# SensorBoard.net
KiCad netlist of a schematic drawn in Altium Designer
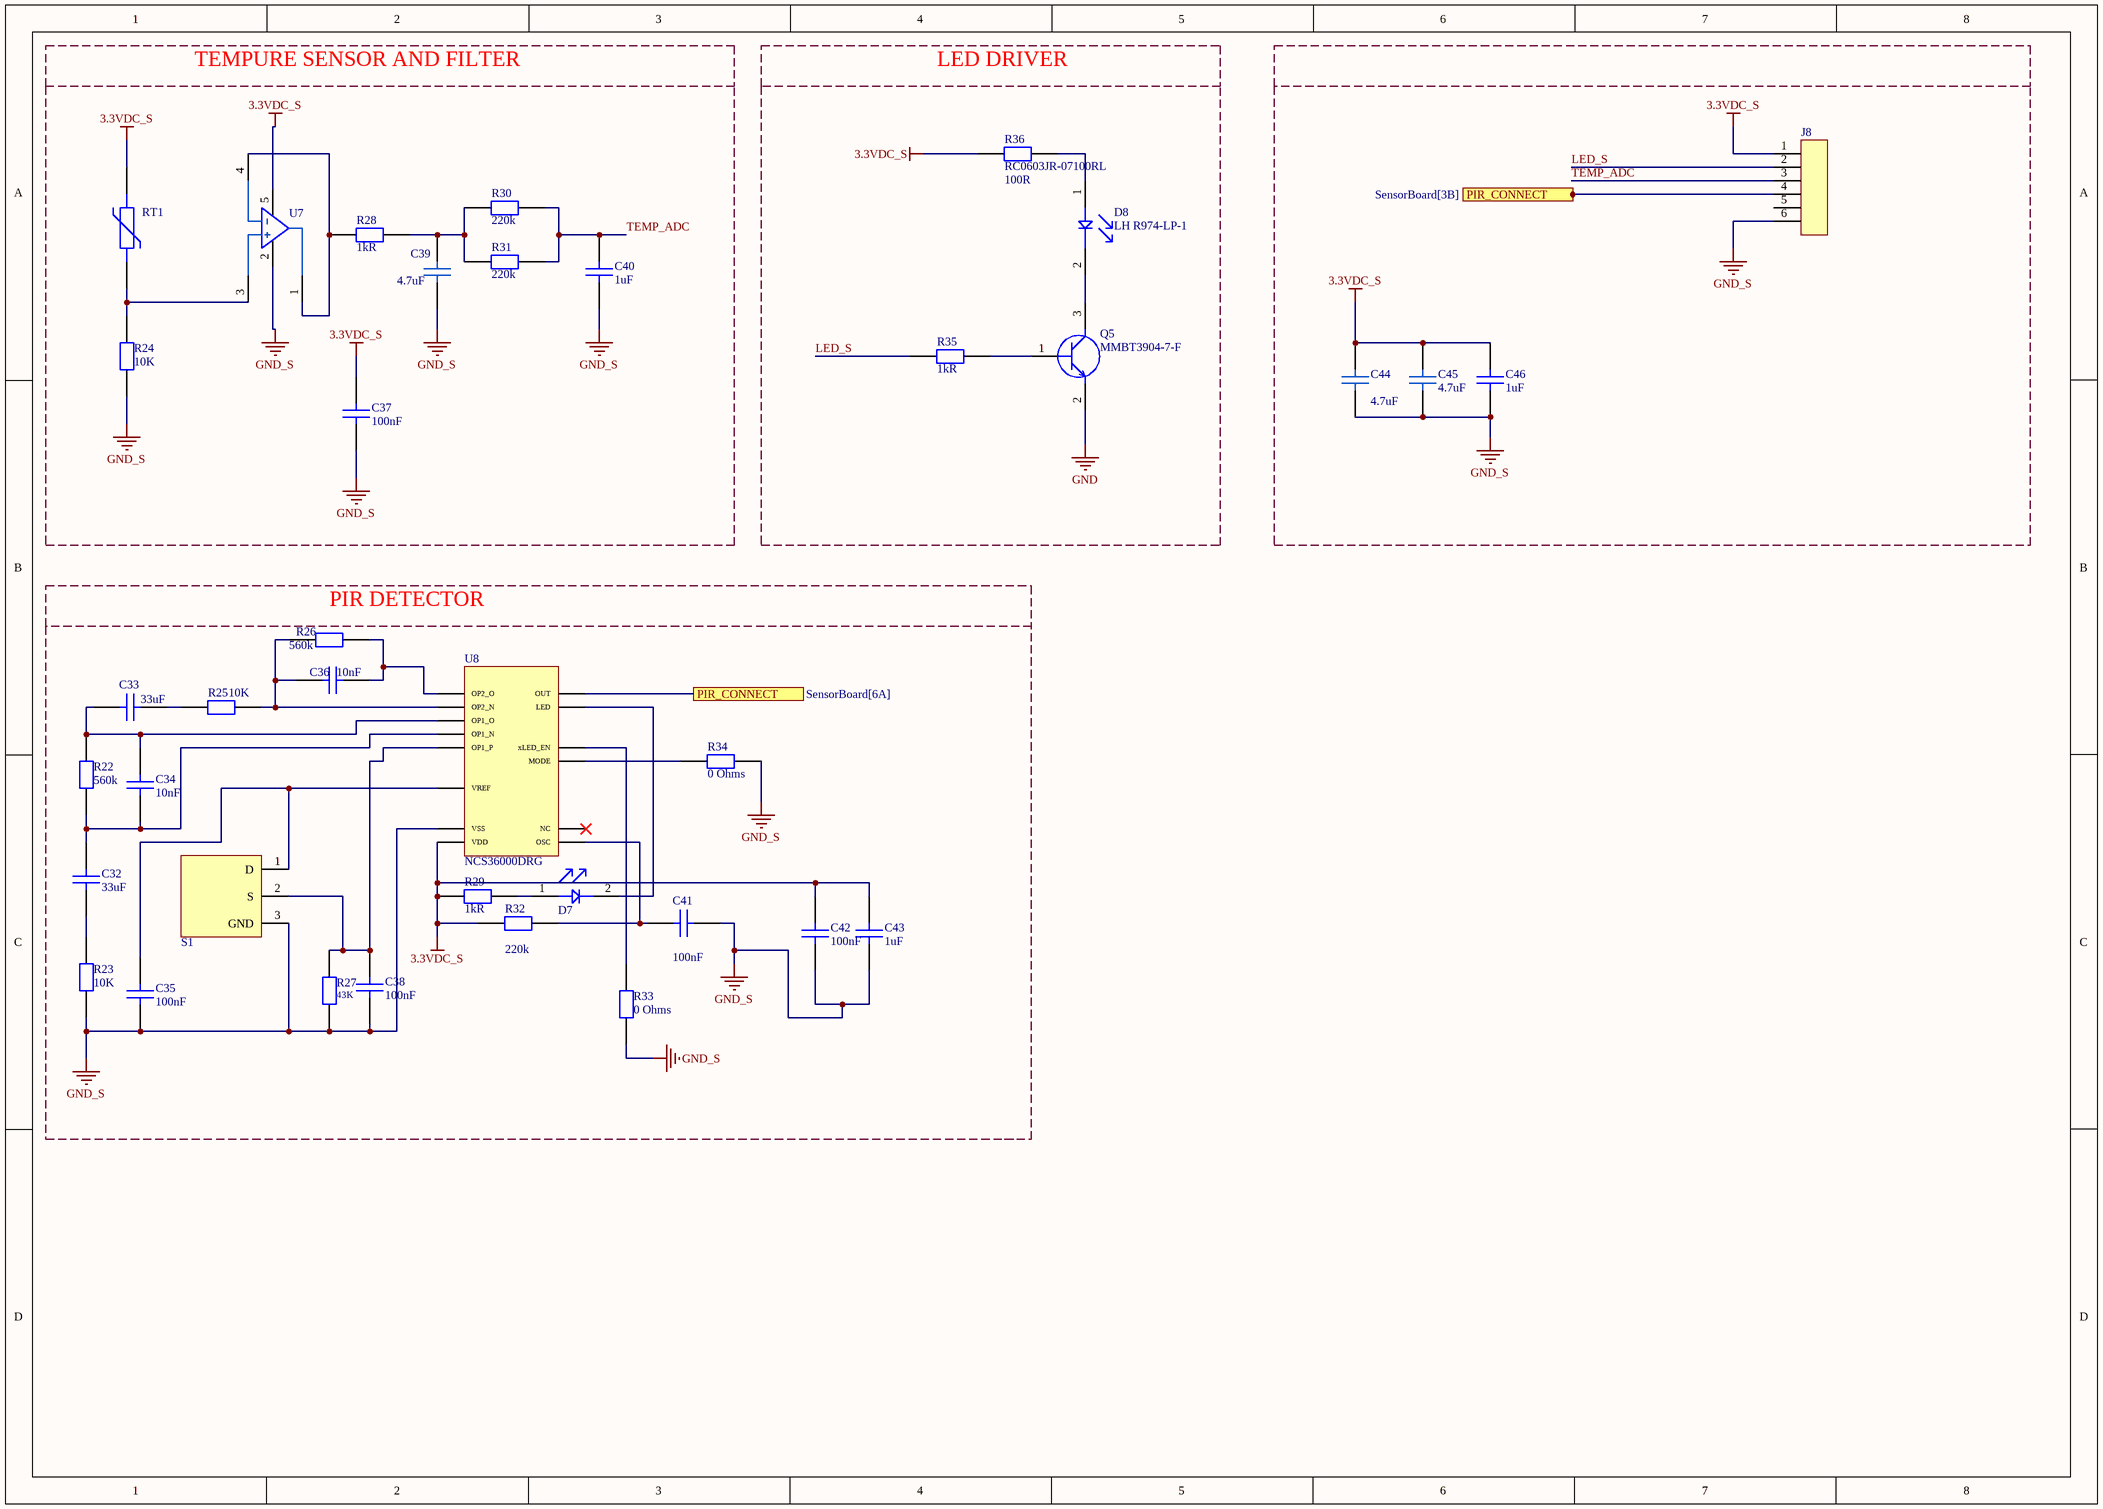
[diagram p0: SensorBoard.SchDoc]

(export (version "E")
  (design (tool "Eeschema 10.0.6"))
  (components
    (comp (ref "C32")
      (value "CAP CER 33UF 25V X5R 1206")
      (footprint "CAP 1206")
      (description "C Series 1206 33 uF 25 V ±20 % Tolerance X5R SMT Multilayer Ceramic Capacitor")
      (fields
        (field (name "MANUFACTURER") "TDK")
        (field (name "MANUFACTURER PART NUMBER") "C3216X5R1E336M160AC")
        (field (name "CAPACITANCE") "33uF")
      )
      (libsource (lib "ComplexCurcuit") (part "CAP CER 33uF 1206"))
    )
    (comp (ref "C33")
      (value "CAP CER 33UF 25V X5R 1206")
      (footprint "CAP 1206")
      (description "C Series 1206 33 uF 25 V ±20 % Tolerance X5R SMT Multilayer Ceramic Capacitor")
      (fields
        (field (name "MANUFACTURER") "TDK")
        (field (name "MANUFACTURER PART NUMBER") "C3216X5R1E336M160AC")
        (field (name "CAPACITANCE") "33uF")
      )
      (libsource (lib "ComplexCurcuit") (part "CAP CER 33uF 1206"))
    )
    (comp (ref "C34")
      (value "0603B103K160CT")
      (footprint "CAP 0603")
      (description "Multilayer Ceramic Capacitor, 0.01 F, 10%, X7R, 16 V, 0603 [1608 Metric] RoHS Compliant: Yes")
      (fields (field (name "MANUFACTURER") "Walsin Technologies") (field (name "CAPACITY") "10nF"))
      (libsource (lib "ComplexCurcuit") (part "CAP CER 10nF"))
    )
    (comp (ref "C35")
      (value "100nF")
      (footprint "CAP 0805")
      (description "Multilayer Ceramic Capacitor, 0.1 uF, 50 V, ± 10%, X7R, 0805 [2012 Metric]")
      (fields
        (field (name "MANUFACTURER") "Samsung")
        (field (name "MANUFACTURER PART NUMBER") "CL21B104KBCNNNC")
      )
      (libsource (lib "ComplexCurcuit") (part "CAP CER 100nF 0805"))
    )
    (comp (ref "C36")
      (value "0603B103K160CT")
      (footprint "CAP 0603")
      (description "Multilayer Ceramic Capacitor, 0.01 F, 10%, X7R, 16 V, 0603 [1608 Metric] RoHS Compliant: Yes")
      (fields (field (name "MANUFACTURER") "Walsin Technologies") (field (name "CAPACITY") "10nF"))
      (libsource (lib "ComplexCurcuit") (part "CAP CER 10nF"))
    )
    (comp (ref "C37")
      (value "CAP CER 100nF")
      (footprint "CAP 0603")
      (description "Cap Cer 0.1UF 16V X7R 0603 %10")
      (fields
        (field (name "MANUFACTURER") "KEMET")
        (field (name "MANUFACTURER PART NUMBER") "C0603C104K4RAC7082")
        (field (name "CAPACITANCE") "100nF")
        (field (name "DESIGNED BY") "Görkem Bulut")
      )
      (libsource (lib "ComplexCurcuit") (part "CAP CER 100nF"))
    )
    (comp (ref "C38")
      (value "100nF")
      (footprint "CAP 0805")
      (description "Multilayer Ceramic Capacitor, 0.1 uF, 50 V, ± 10%, X7R, 0805 [2012 Metric]")
      (fields
        (field (name "MANUFACTURER") "Samsung")
        (field (name "MANUFACTURER PART NUMBER") "CL21B104KBCNNNC")
      )
      (libsource (lib "ComplexCurcuit") (part "CAP CER 100nF 0805"))
    )
    (comp (ref "C39")
      (value "4.7uF")
      (footprint "CAP 0805")
      (description "CAP CER 4.7UF 25V X5R 0805")
      (fields
        (field (name "MANUFACTURER") "Samsung")
        (field (name "MANUFACTURER PART NUMBER") "CL21A475KAQNNNE")
      )
      (libsource (lib "ComplexCurcuit") (part "CAP CER 4.7uF"))
    )
    (comp (ref "C40")
      (value "CAP CER 1UF 50V X7R 0805")
      (footprint "CAP 0805")
      (fields
        (field (name "MANUFACTURER") "Samsung")
        (field (name "MANUFACTURER PART NUMBER") "CL21B105KBFNNNE")
        (field (name "CAPACITANCE") "1uF")
        (field (name "DESIGNED BY") "Görkem Bulut")
      )
      (libsource (lib "ComplexCurcuit") (part "CAP CER 1uF"))
    )
    (comp (ref "C41")
      (value "100nF")
      (footprint "CAP 0805")
      (description "Multilayer Ceramic Capacitor, 0.1 uF, 50 V, ± 10%, X7R, 0805 [2012 Metric]")
      (fields
        (field (name "MANUFACTURER") "Samsung")
        (field (name "MANUFACTURER PART NUMBER") "CL21B104KBCNNNC")
      )
      (libsource (lib "ComplexCurcuit") (part "CAP CER 100nF 0805"))
    )
    (comp (ref "C42")
      (value "100nF")
      (footprint "CAP 0805")
      (description "Multilayer Ceramic Capacitor, 0.1 uF, 50 V, ± 10%, X7R, 0805 [2012 Metric]")
      (fields
        (field (name "MANUFACTURER") "Samsung")
        (field (name "MANUFACTURER PART NUMBER") "CL21B104KBCNNNC")
      )
      (libsource (lib "ComplexCurcuit") (part "CAP CER 100nF 0805"))
    )
    (comp (ref "C43")
      (value "CAP CER 1UF 50V X7R 0805")
      (footprint "CAP 0805")
      (fields
        (field (name "MANUFACTURER") "Samsung")
        (field (name "MANUFACTURER PART NUMBER") "CL21B105KBFNNNE")
        (field (name "CAPACITANCE") "1uF")
        (field (name "DESIGNED BY") "Görkem Bulut")
      )
      (libsource (lib "ComplexCurcuit") (part "CAP CER 1uF"))
    )
    (comp (ref "C44")
      (value "4.7uF")
      (footprint "CAP 0805")
      (description "CAP CER 4.7UF 25V X5R 0805")
      (fields
        (field (name "MANUFACTURER") "Samsung")
        (field (name "MANUFACTURER PART NUMBER") "CL21A475KAQNNNE")
      )
      (libsource (lib "ComplexCurcuit") (part "CAP CER 4.7uF"))
    )
    (comp (ref "C45")
      (value "4.7uF")
      (footprint "CAP 0805")
      (description "CAP CER 4.7UF 25V X5R 0805")
      (fields
        (field (name "MANUFACTURER") "Samsung")
        (field (name "MANUFACTURER PART NUMBER") "CL21A475KAQNNNE")
      )
      (libsource (lib "ComplexCurcuit") (part "CAP CER 4.7uF"))
    )
    (comp (ref "C46")
      (value "CAP CER 1UF 50V X7R 0805")
      (footprint "CAP 0805")
      (fields
        (field (name "MANUFACTURER") "Samsung")
        (field (name "MANUFACTURER PART NUMBER") "CL21B105KBFNNNE")
        (field (name "CAPACITANCE") "1uF")
        (field (name "DESIGNED BY") "Görkem Bulut")
      )
      (libsource (lib "ComplexCurcuit") (part "CAP CER 1uF"))
    )
    (comp (ref "D7")
      (value "LTST-C171GKT")
      (footprint "Chip LED 0805")
      (description "LED Low-Power Uni-Color Green 565nm 2.1V 2-Pin Chip LED T/R")
      (fields (field (name "MANUFACTURER") "Vishay Lite-On") (field (name "DESIGNED BY") "Görkem BULUT"))
      (libsource (lib "ComplexCurcuit") (part "LTST-C171GKT-GreenChipLed"))
    )
    (comp (ref "D8")
      (value "LH R974-LP-1")
      (footprint "Chip LED 0805")
      (description "Red 645nm LED Indication - Discrete 1.8V 0805 (2012 Metric)")
      (fields
        (field (name "MANUFACTURER") "ams-OSRAM USA INC.")
        (field (name "VOLTAGE") "1.8V")
        (field (name "DESIGNED BY") "Görkem Bulut")
      )
      (libsource (lib "ComplexCurcuit") (part "Led- LH R974-LP-1-Chip Led"))
    )
    (comp (ref "J8")
      (value "64800611622 Datasheet WR-WTB Male Vertical Shrouded Header")
      (footprint "64800611622 Connector-1x6 Male Header")
      (description "WR-WTB Wire-to-Board Connectors 1.50 mm")
      (fields
        (field (name "MANUFACTURER") "Wurth Electronics")
        (field (name "MANUFACTURER PART NUMBER") "64800611622")
        (field (name "DESIGNED BY") "Görkem Bulut")
      )
      (libsource (lib "ComplexCurcuit") (part "1x6 Male Header-64800611622 Connector"))
    )
    (comp (ref "Q5")
      (value "MMBT3904-7-F")
      (footprint "SOT23F")
      (description "Transistor General Purpose BJT NPN 40 Volt 0.2A Automotive 3-Pin SOT-23")
      (fields (field (name "MANUFACTURER") "Diodes Zetex") (field (name "DESIGNED BY") "Gökem Bulut"))
      (libsource (lib "ComplexCurcuit") (part "MMBT3904-7-F"))
    )
    (comp (ref "R22")
      (value "RC0603JR-07220KL")
      (footprint "RES 0603")
      (description "SMD Chip Resistor, 220 kOhm, ± 5%, 100 mW, 0603 [1608 Metric], Thick Film, General Purpose")
      (fields
        (field (name "MANUFACTURER") "Yageo")
        (field (name "RESISTANCE") "560k")
        (field (name "DESIGNED BY") "Görkem Bulut")
      )
      (libsource (lib "") (part "RES 560K OHM_1"))
    )
    (comp (ref "R23")
      (value "RES 10K OHM  06103")
      (footprint "RES 0603")
      (description "RES SMD 10K OHM 1% 1/10W 0603")
      (fields
        (field (name "MANUFACTURER") "Yageo")
        (field (name "MANUFACTURER PART NUMBER") "RC0603FR-0710KL")
        (field (name "RESISTANCE") "10K")
        (field (name "DESIGNED BY") "Görkem Bulut")
      )
      (libsource (lib "ComplexCurcuit") (part "RES 10K OHM  06103"))
    )
    (comp (ref "R24")
      (value "RES 10K OHM  06103")
      (footprint "RES 0603")
      (description "RES SMD 10K OHM 1% 1/10W 0603")
      (fields
        (field (name "MANUFACTURER") "Yageo")
        (field (name "MANUFACTURER PART NUMBER") "RC0603FR-0710KL")
        (field (name "RESISTANCE") "10K")
        (field (name "DESIGNED BY") "Görkem Bulut")
      )
      (libsource (lib "ComplexCurcuit") (part "RES 10K OHM  06103"))
    )
    (comp (ref "R25")
      (value "RES 10K OHM  06103")
      (footprint "RES 0603")
      (description "RES SMD 10K OHM 1% 1/10W 0603")
      (fields
        (field (name "MANUFACTURER") "Yageo")
        (field (name "MANUFACTURER PART NUMBER") "RC0603FR-0710KL")
        (field (name "RESISTANCE") "10K")
        (field (name "DESIGNED BY") "Görkem Bulut")
      )
      (libsource (lib "") (part "RES 10K OHM  06103_1"))
    )
    (comp (ref "R26")
      (value "RC0603JR-07220KL")
      (footprint "RES 0603")
      (description "SMD Chip Resistor, 220 kOhm, ± 5%, 100 mW, 0603 [1608 Metric], Thick Film, General Purpose")
      (fields
        (field (name "MANUFACTURER") "Yageo")
        (field (name "RESISTANCE") "560k")
        (field (name "DESIGNED BY") "Görkem Bulut")
      )
      (libsource (lib "ComplexCurcuit") (part "RES 560K OHM"))
    )
    (comp (ref "R27")
      (value "43K")
      (footprint "RES 0603")
      (description "Res Thick Film 0603 43K Ohm 5% 0.1W(1/10W) ±100ppm/°C Pad SMD T/R")
      (fields
        (field (name "MANUFACTURER") "Yageo")
        (field (name "MANUFACTURER PART NUMBER") "RC0603JR-0743KL")
        (field (name "DESIGNED BY") "Görkem Bulut")
      )
      (libsource (lib "ComplexCurcuit") (part "RES 43K"))
    )
    (comp (ref "R28")
      (value "1kR")
      (footprint "RES 0603")
      (description "SMD Chip Resistor, 1 kOhm, ± 1%, 100 mW, 0603 [1608 Metric], Thick Film, General Purpose")
      (fields
        (field (name "MANUFACTURER") "Yageo")
        (field (name "MANUFACTURER PART NUMBER") "RC0603FR-071KL")
        (field (name "DESIGNED BY") "Görkem B.")
      )
      (libsource (lib "ComplexCurcuit") (part "RES 1K OHM"))
    )
    (comp (ref "R29")
      (value "1kR")
      (footprint "RES 0603")
      (description "SMD Chip Resistor, 1 kOhm, ± 1%, 100 mW, 0603 [1608 Metric], Thick Film, General Purpose")
      (fields
        (field (name "MANUFACTURER") "Yageo")
        (field (name "MANUFACTURER PART NUMBER") "RC0603FR-071KL")
        (field (name "DESIGNED BY") "Görkem B.")
      )
      (libsource (lib "ComplexCurcuit") (part "RES 1K OHM"))
    )
    (comp (ref "R30")
      (value "RC0603JR-07220KL")
      (footprint "RES 0603")
      (description "SMD Chip Resistor, 220 kOhm, ± 5%, 100 mW, 0603 [1608 Metric], Thick Film, General Purpose")
      (fields
        (field (name "MANUFACTURER") "Yageo")
        (field (name "RESISTANCE") "220k")
        (field (name "DESIGNED BY") "G.B")
      )
      (libsource (lib "") (part "RES 220K OHM_1"))
    )
    (comp (ref "R31")
      (value "RC0603JR-07220KL")
      (footprint "RES 0603")
      (description "SMD Chip Resistor, 220 kOhm, ± 5%, 100 mW, 0603 [1608 Metric], Thick Film, General Purpose")
      (fields
        (field (name "MANUFACTURER") "Yageo")
        (field (name "RESISTANCE") "220k")
        (field (name "DESIGNED BY") "G.B")
      )
      (libsource (lib "") (part "RES 220K OHM_1"))
    )
    (comp (ref "R32")
      (value "RC0603JR-07220KL")
      (footprint "RES 0603")
      (description "SMD Chip Resistor, 220 kOhm, ± 5%, 100 mW, 0603 [1608 Metric], Thick Film, General Purpose")
      (fields
        (field (name "MANUFACTURER") "Yageo")
        (field (name "RESISTANCE") "220k")
        (field (name "DESIGNED BY") "G.B")
      )
      (libsource (lib "ComplexCurcuit") (part "RES 220K OHM"))
    )
    (comp (ref "R33")
      (value "RES 0 OHM JUMPER 1/10W 0603")
      (footprint "RES 0603")
      (description "Zero Ohm Resistor, Jumper, 0603 [1608 Metric], Thick Film, 100 mW, 1 A, Surface Mount")
      (fields
        (field (name "MANUFACTURER") "Yageo")
        (field (name "MANUFACTURER PART NUMBER") "RC0603JR-070RL")
        (field (name "RESISTANCE") "0 Ohms")
        (field (name "DESIGNED BY") "Görkem Bulut")
      )
      (libsource (lib "ComplexCurcuit") (part "RES 0 OHM 0603"))
    )
    (comp (ref "R34")
      (value "RES 0 OHM JUMPER 1/10W 0603")
      (footprint "RES 0603")
      (description "Zero Ohm Resistor, Jumper, 0603 [1608 Metric], Thick Film, 100 mW, 1 A, Surface Mount")
      (fields
        (field (name "MANUFACTURER") "Yageo")
        (field (name "MANUFACTURER PART NUMBER") "RC0603JR-070RL")
        (field (name "RESISTANCE") "0 Ohms")
        (field (name "DESIGNED BY") "Görkem Bulut")
      )
      (libsource (lib "") (part "RES 0 OHM 0603_1"))
    )
    (comp (ref "R35")
      (value "1kR")
      (footprint "RES 0603")
      (description "SMD Chip Resistor, 1 kOhm, ± 1%, 100 mW, 0603 [1608 Metric], Thick Film, General Purpose")
      (fields
        (field (name "MANUFACTURER") "Yageo")
        (field (name "MANUFACTURER PART NUMBER") "RC0603FR-071KL")
        (field (name "DESIGNED BY") "Görkem B.")
      )
      (libsource (lib "ComplexCurcuit") (part "RES 1K OHM"))
    )
    (comp (ref "R36")
      (value "RC0603JR-07100RL")
      (footprint "RES 0603")
      (description "Res Thick Film 0603 100 Ohm 5% 1/10W ±100ppm/°C Molded SMD SMD Paper T/R")
      (fields
        (field (name "MANUFACTURER") "Yageo")
        (field (name "TOLERANCE") "5%")
        (field (name "RESISTANCE") "100R")
        (field (name "DESIGNED BY") "G.B")
      )
      (libsource (lib "ComplexCurcuit") (part "RES 100 OHM"))
    )
    (comp (ref "RT1")
      (value "TFPT1206L1002FM")
      (footprint "RES 1206 Package")
      (description "Thermistor PTC 10K Ohm 1% 2-Pin 1206 Surface Mount Solder Pad T/R Automotive")
      (fields
        (field (name "MANUFACTURER") "Vishay Dale")
        (field (name "TOLERANCE") "1%")
        (field (name "DESIGNED BY") "Görkem BULUT")
      )
      (libsource (lib "ComplexCurcuit") (part "TFPT1206L1002FM"))
    )
    (comp (ref "S1")
      (value "LHI 878/3902")
      (footprint "LHI 878/3902")
      (description "SENSOR PYRO DETECTOR DUAL MOTION")
      (fields
        (field (name "MANUFACTURER") "Excelitas Technologies")
        (field (name "DESIGNED BY") "Görkem Bulut")
      )
      (libsource (lib "ComplexCurcuit") (part "LHI 878/3902"))
    )
    (comp (ref "U7")
      (value "IC OPAMP GP 1 CIRCUIT SOT23-5")
      (footprint "SOT23-5")
      (description "IC OPAMP GP 3MHZ RRO SOT23-5")
      (fields
        (field (name "MANUFACTURER") "Texas Instruments")
        (field (name "MANUFACTURER PART NUMBER") "OPA314AIDBVR")
        (field (name "DESIGNED BY") "Görkem Bulut")
      )
      (libsource (lib "ComplexCurcuit") (part "OPA314AIDBVR"))
    )
    (comp (ref "U8")
      (value "NCS36000DRG")
      (footprint "SOIC14")
      (description "NCS36000 Series Single 5.75V Passive Infrared Detector Controller (PIR) -SOIC-14")
      (fields (field (name "MANUFACTURER") "ON Semiconductor"))
      (libsource (lib "ComplexCurcuit") (part "NCS36000DRG"))
    )
  )
  (nets
    (net (code "1") (name "/LED_S") (class "Default")
      (node (ref "J8") (pin "2") (pinfunction "2_2") (pintype "passive"))
      (node (ref "R35") (pin "1") (pinfunction "1_1") (pintype "passive"))
    )
    (net (code "2") (name "/PIR_CONNECT") (class "Default")
      (node (ref "J8") (pin "4") (pinfunction "4_4") (pintype "passive"))
      (node (ref "U8") (pin "8") (pinfunction "OUT_8") (pintype "passive"))
    )
    (net (code "3") (name "/TEMP_ADC") (class "Default")
      (node (ref "C40") (pin "2") (pinfunction "2_2") (pintype "passive"))
      (node (ref "J8") (pin "3") (pinfunction "3_3") (pintype "passive"))
      (node (ref "R30") (pin "1") (pinfunction "1_1") (pintype "passive"))
      (node (ref "R31") (pin "1") (pinfunction "1_1") (pintype "passive"))
    )
    (net (code "4") (name "3.3VDC_S") (class "Default")
      (node (ref "C37") (pin "2") (pinfunction "2_2") (pintype "passive"))
      (node (ref "C42") (pin "2") (pinfunction "2_2") (pintype "passive"))
      (node (ref "C43") (pin "2") (pinfunction "2_2") (pintype "passive"))
      (node (ref "C44") (pin "2") (pinfunction "2_2") (pintype "passive"))
      (node (ref "C45") (pin "2") (pinfunction "2_2") (pintype "passive"))
      (node (ref "C46") (pin "2") (pinfunction "2_2") (pintype "passive"))
      (node (ref "J8") (pin "1") (pinfunction "1_1") (pintype "passive"))
      (node (ref "R29") (pin "1") (pinfunction "1_1") (pintype "passive"))
      (node (ref "R32") (pin "1") (pinfunction "1_1") (pintype "passive"))
      (node (ref "R36") (pin "2") (pinfunction "2_2") (pintype "passive"))
      (node (ref "RT1") (pin "2") (pinfunction "2_2") (pintype "passive"))
      (node (ref "U7") (pin "5") (pinfunction "V+_5") (pintype "passive"))
      (node (ref "U8") (pin "14") (pinfunction "VDD_14") (pintype "passive"))
    )
    (net (code "5") (name "GND") (class "Default")
      (node (ref "Q5") (pin "2") (pinfunction "EMİTTER_2") (pintype "passive"))
    )
    (net (code "6") (name "GND_S") (class "Default")
      (node (ref "C35") (pin "1") (pinfunction "1_1") (pintype "passive"))
      (node (ref "C37") (pin "1") (pinfunction "1_1") (pintype "passive"))
      (node (ref "C38") (pin "1") (pinfunction "1_1") (pintype "passive"))
      (node (ref "C39") (pin "1") (pinfunction "1_1") (pintype "passive"))
      (node (ref "C40") (pin "1") (pinfunction "1_1") (pintype "passive"))
      (node (ref "C41") (pin "2") (pinfunction "2_2") (pintype "passive"))
      (node (ref "C42") (pin "1") (pinfunction "1_1") (pintype "passive"))
      (node (ref "C43") (pin "1") (pinfunction "1_1") (pintype "passive"))
      (node (ref "C44") (pin "1") (pinfunction "1_1") (pintype "passive"))
      (node (ref "C45") (pin "1") (pinfunction "1_1") (pintype "passive"))
      (node (ref "C46") (pin "1") (pinfunction "1_1") (pintype "passive"))
      (node (ref "J8") (pin "6") (pinfunction "6_6") (pintype "passive"))
      (node (ref "R23") (pin "1") (pinfunction "1_1") (pintype "passive"))
      (node (ref "R24") (pin "1") (pinfunction "1_1") (pintype "passive"))
      (node (ref "R27") (pin "1") (pinfunction "1_1") (pintype "passive"))
      (node (ref "R33") (pin "1") (pinfunction "1_1") (pintype "passive"))
      (node (ref "R34") (pin "1") (pinfunction "1_1") (pintype "passive"))
      (node (ref "S1") (pin "3") (pinfunction "GND_3") (pintype "passive"))
      (node (ref "U7") (pin "2") (pinfunction "V-_2") (pintype "passive"))
      (node (ref "U8") (pin "7") (pinfunction "VSS_7") (pintype "passive"))
    )
    (net (code "7") (name "Net-(C32-Pad1)") (class "Default")
      (node (ref "C32") (pin "1") (pinfunction "1_1") (pintype "passive"))
      (node (ref "R23") (pin "2") (pinfunction "2_2") (pintype "passive"))
    )
    (net (code "8") (name "Net-(C33-Pad2)") (class "Default")
      (node (ref "C33") (pin "2") (pinfunction "2_2") (pintype "passive"))
      (node (ref "R25") (pin "1") (pinfunction "1_1") (pintype "passive"))
    )
    (net (code "9") (name "Net-(C39-Pad2)") (class "Default")
      (node (ref "C39") (pin "2") (pinfunction "2_2") (pintype "passive"))
      (node (ref "R28") (pin "2") (pinfunction "2_2") (pintype "passive"))
      (node (ref "R30") (pin "2") (pinfunction "2_2") (pintype "passive"))
      (node (ref "R31") (pin "2") (pinfunction "2_2") (pintype "passive"))
    )
    (net (code "10") (name "Net-(D7-Pad1)") (class "Default")
      (node (ref "D7") (pin "1") (pinfunction "1_1") (pintype "passive"))
      (node (ref "R29") (pin "2") (pinfunction "2_2") (pintype "passive"))
    )
    (net (code "11") (name "Net-(D8-Pad1)") (class "Default")
      (node (ref "D8") (pin "1") (pinfunction "1_1") (pintype "passive"))
      (node (ref "R36") (pin "1") (pinfunction "1_1") (pintype "passive"))
    )
    (net (code "12") (name "Net-(Q5-BASE)") (class "Default")
      (node (ref "Q5") (pin "1") (pinfunction "BASE_1") (pintype "passive"))
      (node (ref "R35") (pin "2") (pinfunction "2_2") (pintype "passive"))
    )
    (net (code "13") (name "Net-(Q5-CONNECTOR)") (class "Default")
      (node (ref "D8") (pin "2") (pinfunction "2_2") (pintype "passive"))
      (node (ref "Q5") (pin "3") (pinfunction "CONNECTOR_3") (pintype "passive"))
    )
    (net (code "14") (name "Net-(S1-D)") (class "Default")
      (node (ref "C35") (pin "2") (pinfunction "2_2") (pintype "passive"))
      (node (ref "S1") (pin "1") (pinfunction "D_1") (pintype "passive"))
      (node (ref "U8") (pin "6") (pinfunction "VREF_6") (pintype "passive"))
    )
    (net (code "15") (name "Net-(S1-S)") (class "Default")
      (node (ref "C38") (pin "2") (pinfunction "2_2") (pintype "passive"))
      (node (ref "R27") (pin "2") (pinfunction "2_2") (pintype "passive"))
      (node (ref "S1") (pin "2") (pinfunction "S_2") (pintype "passive"))
      (node (ref "U8") (pin "5") (pinfunction "OP1_P_5") (pintype "passive"))
    )
    (net (code "16") (name "Net-(U7-+IN)") (class "Default")
      (node (ref "R24") (pin "2") (pinfunction "2_2") (pintype "passive"))
      (node (ref "RT1") (pin "1") (pinfunction "1_1") (pintype "passive"))
      (node (ref "U7") (pin "3") (pinfunction "+IN_3") (pintype "passive"))
    )
    (net (code "17") (name "Net-(U7-OUT)") (class "Default")
      (node (ref "R28") (pin "1") (pinfunction "1_1") (pintype "passive"))
      (node (ref "U7") (pin "1") (pinfunction "OUT_1") (pintype "passive"))
    )
    (net (code "18") (name "Net-(U8-LED)") (class "Default")
      (node (ref "D7") (pin "2") (pinfunction "2_2") (pintype "passive"))
      (node (ref "U8") (pin "9") (pinfunction "LED_9") (pintype "passive"))
    )
    (net (code "19") (name "Net-(U8-MODE)") (class "Default")
      (node (ref "R34") (pin "2") (pinfunction "2_2") (pintype "passive"))
      (node (ref "U8") (pin "12") (pinfunction "MODE_12") (pintype "passive"))
    )
    (net (code "20") (name "Net-(U8-OP1_N)") (class "Default")
      (node (ref "C32") (pin "2") (pinfunction "2_2") (pintype "passive"))
      (node (ref "C34") (pin "1") (pinfunction "1_1") (pintype "passive"))
      (node (ref "R22") (pin "1") (pinfunction "1_1") (pintype "passive"))
      (node (ref "U8") (pin "4") (pinfunction "OP1_N_4") (pintype "passive"))
    )
    (net (code "21") (name "Net-(U8-OP1_O)") (class "Default")
      (node (ref "C33") (pin "1") (pinfunction "1_1") (pintype "passive"))
      (node (ref "C34") (pin "2") (pinfunction "2_2") (pintype "passive"))
      (node (ref "R22") (pin "2") (pinfunction "2_2") (pintype "passive"))
      (node (ref "U8") (pin "3") (pinfunction "OP1_O_3") (pintype "passive"))
    )
    (net (code "22") (name "Net-(U8-OP2_N)") (class "Default")
      (node (ref "C36") (pin "1") (pinfunction "1_1") (pintype "passive"))
      (node (ref "R25") (pin "2") (pinfunction "2_2") (pintype "passive"))
      (node (ref "R26") (pin "1") (pinfunction "1_1") (pintype "passive"))
      (node (ref "U8") (pin "2") (pinfunction "OP2_N_2") (pintype "passive"))
    )
    (net (code "23") (name "Net-(U8-OP2_O)") (class "Default")
      (node (ref "C36") (pin "2") (pinfunction "2_2") (pintype "passive"))
      (node (ref "R26") (pin "2") (pinfunction "2_2") (pintype "passive"))
      (node (ref "U8") (pin "1") (pinfunction "OP2_O_1") (pintype "passive"))
    )
    (net (code "24") (name "Net-(U8-OSC)") (class "Default")
      (node (ref "C41") (pin "1") (pinfunction "1_1") (pintype "passive"))
      (node (ref "R32") (pin "2") (pinfunction "2_2") (pintype "passive"))
      (node (ref "U8") (pin "13") (pinfunction "OSC_13") (pintype "passive"))
    )
    (net (code "25") (name "Net-(U8-xLED_EN)") (class "Default")
      (node (ref "R33") (pin "2") (pinfunction "2_2") (pintype "passive"))
      (node (ref "U8") (pin "10") (pinfunction "xLED_EN_10") (pintype "passive"))
    )
    (net (code "26") (name "unconnected-(J8-Pad5)") (class "Default")
      (node (ref "J8") (pin "5") (pinfunction "5_5") (pintype "passive"))
    )
    (net (code "27") (name "unconnected-(U7--IN-Pad4)") (class "Default")
      (node (ref "U7") (pin "4") (pinfunction "-IN_4") (pintype "passive"))
    )
    (net (code "28") (name "unconnected-(U8-NC-Pad11)") (class "Default")
      (node (ref "U8") (pin "11") (pinfunction "NC_11") (pintype "passive+no_connect"))
    )
  )
)
